# bareduinonano.net
KiCad netlist of a schematic drawn in EAGLE
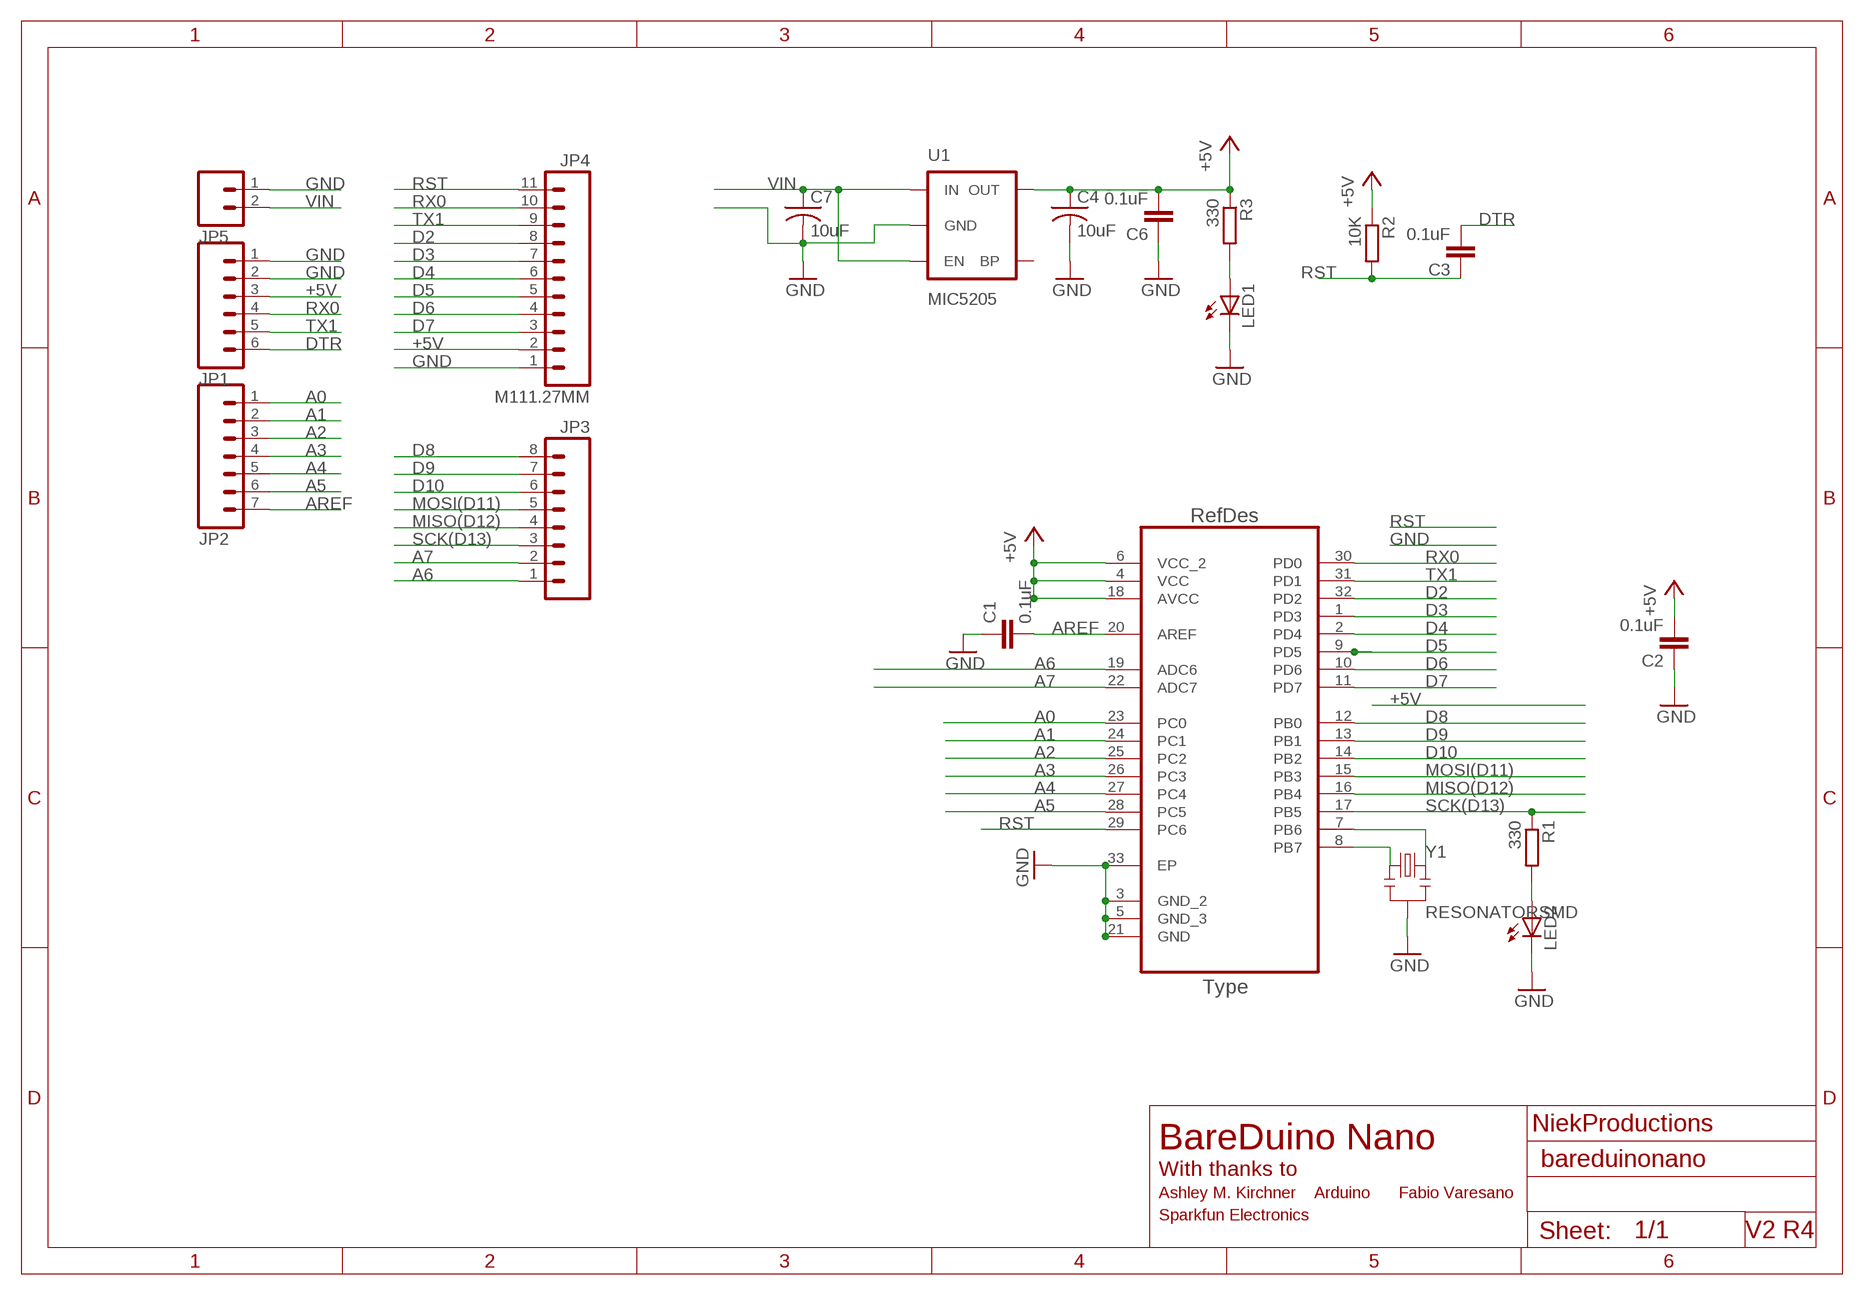
[diagram p0: schematic, sheet 1]

(export (version "E")
  (design (tool "Eeschema 10.0.6"))
  (components
    (comp (ref "C1")
      (value "0.1uF")
      (footprint "eagle-import:C0402K")
      (libsource (lib "eagle-import") (part "C-EUC0402K"))
    )
    (comp (ref "C2")
      (value "0.1uF")
      (footprint "eagle-import:C0402K")
      (libsource (lib "eagle-import") (part "C-EUC0402K"))
    )
    (comp (ref "C3")
      (value "0.1uF")
      (footprint "eagle-import:C0402K")
      (libsource (lib "eagle-import") (part "C-EUC0402K"))
    )
    (comp (ref "C4")
      (value "10uF")
      (footprint "eagle-import:C0603K")
      (libsource (lib "eagle-import") (part "C-USC0603K"))
    )
    (comp (ref "C6")
      (value "0.1uF")
      (footprint "eagle-import:C0402K")
      (libsource (lib "eagle-import") (part "C-EUC0402K"))
    )
    (comp (ref "C7")
      (value "10uF")
      (footprint "eagle-import:C0603K")
      (libsource (lib "eagle-import") (part "C-USC0603K"))
    )
    (comp (ref "JP1")
      (value "M061.27MM")
      (footprint "eagle-import:1X06-1.27MM")
      (libsource (lib "eagle-import") (part "M061.27MM"))
    )
    (comp (ref "JP2")
      (value "M071.27MM")
      (footprint "eagle-import:1X07-1.27MM")
      (libsource (lib "eagle-import") (part "M071.27MM"))
    )
    (comp (ref "JP3")
      (value "M081.27MM")
      (footprint "eagle-import:1X08-1.27MM")
      (libsource (lib "eagle-import") (part "M081.27MM"))
    )
    (comp (ref "JP4")
      (value "M111.27MM")
      (footprint "eagle-import:1X11-1.27MM")
      (libsource (lib "eagle-import") (part "M111.27MM"))
    )
    (comp (ref "JP5")
      (value "M021.27MM")
      (footprint "eagle-import:1X02-1.27MM")
      (libsource (lib "eagle-import") (part "M021.27MM"))
    )
    (comp (ref "LED1")
      (value "LED0603")
      (footprint "eagle-import:LED-0603")
      (libsource (lib "eagle-import") (part "LED0603"))
    )
    (comp (ref "LED2")
      (value "LED0603")
      (footprint "eagle-import:LED-0603")
      (libsource (lib "eagle-import") (part "LED0603"))
    )
    (comp (ref "R1")
      (value "330")
      (footprint "eagle-import:R0402")
      (libsource (lib "eagle-import") (part "R-EU_R0402"))
    )
    (comp (ref "R2")
      (value "10K")
      (footprint "eagle-import:R0402")
      (libsource (lib "eagle-import") (part "R-EU_R0402"))
    )
    (comp (ref "R3")
      (value "330")
      (footprint "eagle-import:R0402")
      (libsource (lib "eagle-import") (part "R-EU_R0402"))
    )
    (comp (ref "U1")
      (value "MIC5205")
      (footprint "eagle-import:SOT23-5")
      (libsource (lib "eagle-import") (part "V_REG_LDOSMD"))
    )
    (comp (ref "UC1")
      (value "ATMEGA328P-MU")
      (footprint "eagle-import:QFN50P500X500X100-33N")
      (libsource (lib "eagle-import") (part "ATMEGA328P-MU"))
    )
    (comp (ref "Y1")
      (value "RESONATORSMD")
      (footprint "eagle-import:RESONATOR-SMD")
      (libsource (lib "eagle-import") (part "RESONATORSMD"))
    )
  )
  (nets
    (net (code "1") (name "+5V") (class "Default")
      (node (ref "C2") (pin "2") (pinfunction "2_2") (pintype "passive"))
      (node (ref "C4") (pin "1") (pinfunction "1_1") (pintype "passive"))
      (node (ref "C6") (pin "2") (pinfunction "2_2") (pintype "passive"))
      (node (ref "JP1") (pin "3") (pinfunction "3_3") (pintype "passive"))
      (node (ref "JP4") (pin "2") (pinfunction "2_2") (pintype "passive"))
      (node (ref "R2") (pin "1") (pinfunction "1_1") (pintype "passive"))
      (node (ref "R3") (pin "1") (pinfunction "1_1") (pintype "passive"))
      (node (ref "U1") (pin "5") (pinfunction "OUT_5") (pintype "passive"))
      (node (ref "UC1") (pin "18") (pinfunction "AVCC_18") (pintype "power_in"))
      (node (ref "UC1") (pin "4") (pinfunction "VCC_4") (pintype "power_in"))
      (node (ref "UC1") (pin "6") (pinfunction "VCC_2_6") (pintype "power_in"))
    )
    (net (code "2") (name "/A0") (class "Default")
      (node (ref "JP2") (pin "1") (pinfunction "1_1") (pintype "passive"))
      (node (ref "UC1") (pin "23") (pinfunction "PC0_23") (pintype "bidirectional"))
    )
    (net (code "3") (name "/A1") (class "Default")
      (node (ref "JP2") (pin "2") (pinfunction "2_2") (pintype "passive"))
      (node (ref "UC1") (pin "24") (pinfunction "PC1_24") (pintype "bidirectional"))
    )
    (net (code "4") (name "/A2") (class "Default")
      (node (ref "JP2") (pin "3") (pinfunction "3_3") (pintype "passive"))
      (node (ref "UC1") (pin "25") (pinfunction "PC2_25") (pintype "bidirectional"))
    )
    (net (code "5") (name "/A3") (class "Default")
      (node (ref "JP2") (pin "4") (pinfunction "4_4") (pintype "passive"))
      (node (ref "UC1") (pin "26") (pinfunction "PC3_26") (pintype "bidirectional"))
    )
    (net (code "6") (name "/A4") (class "Default")
      (node (ref "JP2") (pin "5") (pinfunction "5_5") (pintype "passive"))
      (node (ref "UC1") (pin "27") (pinfunction "PC4_27") (pintype "bidirectional"))
    )
    (net (code "7") (name "/A5") (class "Default")
      (node (ref "JP2") (pin "6") (pinfunction "6_6") (pintype "passive"))
      (node (ref "UC1") (pin "28") (pinfunction "PC5_28") (pintype "bidirectional"))
    )
    (net (code "8") (name "/A6") (class "Default")
      (node (ref "JP3") (pin "1") (pinfunction "1_1") (pintype "passive"))
      (node (ref "UC1") (pin "19") (pinfunction "ADC6_19") (pintype "input"))
    )
    (net (code "9") (name "/A7") (class "Default")
      (node (ref "JP3") (pin "2") (pinfunction "2_2") (pintype "passive"))
      (node (ref "UC1") (pin "22") (pinfunction "ADC7_22") (pintype "input"))
    )
    (net (code "10") (name "/AREF") (class "Default")
      (node (ref "C1") (pin "2") (pinfunction "2_2") (pintype "passive"))
      (node (ref "JP2") (pin "7") (pinfunction "7_7") (pintype "passive"))
      (node (ref "UC1") (pin "20") (pinfunction "AREF_20") (pintype "input"))
    )
    (net (code "11") (name "/D2") (class "Default")
      (node (ref "JP4") (pin "8") (pinfunction "8_8") (pintype "passive"))
      (node (ref "UC1") (pin "32") (pinfunction "PD2_32") (pintype "bidirectional"))
    )
    (net (code "12") (name "/D3") (class "Default")
      (node (ref "JP4") (pin "7") (pinfunction "7_7") (pintype "passive"))
      (node (ref "UC1") (pin "1") (pinfunction "PD3_1") (pintype "bidirectional"))
    )
    (net (code "13") (name "/D4") (class "Default")
      (node (ref "JP4") (pin "6") (pinfunction "6_6") (pintype "passive"))
      (node (ref "UC1") (pin "2") (pinfunction "PD4_2") (pintype "bidirectional"))
    )
    (net (code "14") (name "/D5") (class "Default")
      (node (ref "JP4") (pin "5") (pinfunction "5_5") (pintype "passive"))
      (node (ref "UC1") (pin "9") (pinfunction "PD5_9") (pintype "bidirectional"))
    )
    (net (code "15") (name "/D6") (class "Default")
      (node (ref "JP4") (pin "4") (pinfunction "4_4") (pintype "passive"))
      (node (ref "UC1") (pin "10") (pinfunction "PD6_10") (pintype "bidirectional"))
    )
    (net (code "16") (name "/D7") (class "Default")
      (node (ref "JP4") (pin "3") (pinfunction "3_3") (pintype "passive"))
      (node (ref "UC1") (pin "11") (pinfunction "PD7_11") (pintype "bidirectional"))
    )
    (net (code "17") (name "/D8") (class "Default")
      (node (ref "JP3") (pin "8") (pinfunction "8_8") (pintype "passive"))
      (node (ref "UC1") (pin "12") (pinfunction "PB0_12") (pintype "bidirectional"))
    )
    (net (code "18") (name "/D9") (class "Default")
      (node (ref "JP3") (pin "7") (pinfunction "7_7") (pintype "passive"))
      (node (ref "UC1") (pin "13") (pinfunction "PB1_13") (pintype "bidirectional"))
    )
    (net (code "19") (name "/D10") (class "Default")
      (node (ref "JP3") (pin "6") (pinfunction "6_6") (pintype "passive"))
      (node (ref "UC1") (pin "14") (pinfunction "PB2_14") (pintype "bidirectional"))
    )
    (net (code "20") (name "/DTR") (class "Default")
      (node (ref "C3") (pin "2") (pinfunction "2_2") (pintype "passive"))
      (node (ref "JP1") (pin "6") (pinfunction "6_6") (pintype "passive"))
    )
    (net (code "21") (name "/MISO(D12)") (class "Default")
      (node (ref "JP3") (pin "4") (pinfunction "4_4") (pintype "passive"))
      (node (ref "UC1") (pin "16") (pinfunction "PB4_16") (pintype "bidirectional"))
    )
    (net (code "22") (name "/MOSI(D11)") (class "Default")
      (node (ref "JP3") (pin "5") (pinfunction "5_5") (pintype "passive"))
      (node (ref "UC1") (pin "15") (pinfunction "PB3_15") (pintype "bidirectional"))
    )
    (net (code "23") (name "/RST") (class "Default")
      (node (ref "C3") (pin "1") (pinfunction "1_1") (pintype "passive"))
      (node (ref "JP4") (pin "11") (pinfunction "11_11") (pintype "passive"))
      (node (ref "R2") (pin "2") (pinfunction "2_2") (pintype "passive"))
      (node (ref "UC1") (pin "29") (pinfunction "PC6_29") (pintype "bidirectional"))
    )
    (net (code "24") (name "/RX0") (class "Default")
      (node (ref "JP1") (pin "4") (pinfunction "4_4") (pintype "passive"))
      (node (ref "JP4") (pin "10") (pinfunction "10_10") (pintype "passive"))
      (node (ref "UC1") (pin "30") (pinfunction "PD0_30") (pintype "bidirectional"))
    )
    (net (code "25") (name "/SCK(D13)") (class "Default")
      (node (ref "JP3") (pin "3") (pinfunction "3_3") (pintype "passive"))
      (node (ref "R1") (pin "1") (pinfunction "1_1") (pintype "passive"))
      (node (ref "UC1") (pin "17") (pinfunction "PB5_17") (pintype "bidirectional"))
    )
    (net (code "26") (name "/TX1") (class "Default")
      (node (ref "JP1") (pin "5") (pinfunction "5_5") (pintype "passive"))
      (node (ref "JP4") (pin "9") (pinfunction "9_9") (pintype "passive"))
      (node (ref "UC1") (pin "31") (pinfunction "PD1_31") (pintype "bidirectional"))
    )
    (net (code "27") (name "/VIN") (class "Default")
      (node (ref "C7") (pin "1") (pinfunction "1_1") (pintype "passive"))
      (node (ref "JP5") (pin "2") (pinfunction "2_2") (pintype "passive"))
      (node (ref "U1") (pin "1") (pinfunction "IN_1") (pintype "input"))
      (node (ref "U1") (pin "3") (pinfunction "EN_3") (pintype "input"))
    )
    (net (code "28") (name "GND") (class "Default")
      (node (ref "C1") (pin "1") (pinfunction "1_1") (pintype "passive"))
      (node (ref "C2") (pin "1") (pinfunction "1_1") (pintype "passive"))
      (node (ref "C4") (pin "2") (pinfunction "2_2") (pintype "passive"))
      (node (ref "C6") (pin "1") (pinfunction "1_1") (pintype "passive"))
      (node (ref "C7") (pin "2") (pinfunction "2_2") (pintype "passive"))
      (node (ref "JP1") (pin "1") (pinfunction "1_1") (pintype "passive"))
      (node (ref "JP1") (pin "2") (pinfunction "2_2") (pintype "passive"))
      (node (ref "JP4") (pin "1") (pinfunction "1_1") (pintype "passive"))
      (node (ref "JP5") (pin "1") (pinfunction "1_1") (pintype "passive"))
      (node (ref "LED1") (pin "C") (pinfunction "C_C") (pintype "passive"))
      (node (ref "LED2") (pin "C") (pinfunction "C_C") (pintype "passive"))
      (node (ref "U1") (pin "2") (pinfunction "GND_2") (pintype "input"))
      (node (ref "UC1") (pin "21") (pinfunction "GND_21") (pintype "passive"))
      (node (ref "UC1") (pin "3") (pinfunction "GND_2_3") (pintype "passive"))
      (node (ref "UC1") (pin "33") (pinfunction "EP_33") (pintype "passive"))
      (node (ref "UC1") (pin "5") (pinfunction "GND_3_5") (pintype "passive"))
      (node (ref "Y1") (pin "2") (pinfunction "2_2") (pintype "passive"))
    )
    (net (code "29") (name "Net-(LED1-PadA)") (class "Default")
      (node (ref "LED1") (pin "A") (pinfunction "A_A") (pintype "passive"))
      (node (ref "R3") (pin "2") (pinfunction "2_2") (pintype "passive"))
    )
    (net (code "30") (name "Net-(LED2-PadA)") (class "Default")
      (node (ref "LED2") (pin "A") (pinfunction "A_A") (pintype "passive"))
      (node (ref "R1") (pin "2") (pinfunction "2_2") (pintype "passive"))
    )
    (net (code "31") (name "Net-(UC1-PB6)") (class "Default")
      (node (ref "UC1") (pin "7") (pinfunction "PB6_7") (pintype "bidirectional"))
      (node (ref "Y1") (pin "3") (pinfunction "3_3") (pintype "passive"))
    )
    (net (code "32") (name "Net-(UC1-PB7)") (class "Default")
      (node (ref "UC1") (pin "8") (pinfunction "PB7_8") (pintype "bidirectional"))
      (node (ref "Y1") (pin "1") (pinfunction "1_1") (pintype "passive"))
    )
    (net (code "33") (name "unconnected-(U1-BP-Pad4)") (class "Default")
      (node (ref "U1") (pin "4") (pinfunction "BP_4") (pintype "input"))
    )
  )
)
